# pulseAmplifier.net
KiCad netlist of a schematic drawn in Altium Designer
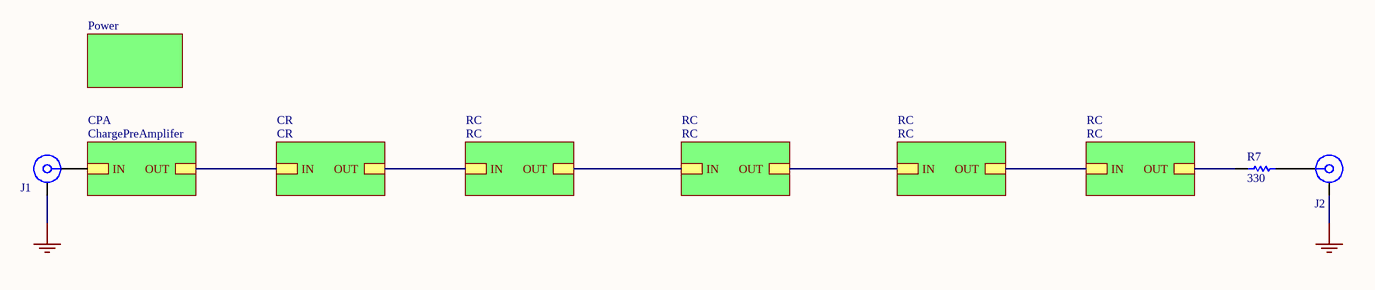
[diagram p0: pulseAmplifier.SchDoc]

(export (version "E")
  (design (tool "Eeschema 10.0.6"))
  (components
    (comp (ref "J1")
      (value "32K145-400L5")
      (footprint "ROS-32K145-400L5_V")
      (description "SMA Right Angle Jack, Edge Mount, Up to 18 GHz, -55 to 155 degC")
      (fields (field (name "MANUFACTURER") "Rosenberger"))
      (libsource (lib "Altium Content Vault") (part "ROS-CN-1F-RF1-A"))
    )
    (comp (ref "J2")
      (value "32K145-400L5")
      (footprint "ROS-32K145-400L5_V")
      (description "SMA Right Angle Jack, Edge Mount, Up to 18 GHz, -55 to 155 degC")
      (fields (field (name "MANUFACTURER") "Rosenberger"))
      (libsource (lib "Altium Content Vault") (part "ROS-CN-1F-RF1-A"))
    )
    (comp (ref "R7")
      (value "330")
      (footprint "RESC0603(1608)_N")
      (description "100R 0.1W 1% 0603 (1608 Metric)  SMD")
      (fields (field (name "TOLERANCE") "1 %") (field (name "POWER") "0.1 W"))
      (libsource (lib "Altium Content Vault") (part "RES"))
    )
  )
  (nets
    (net (code "1") (name "/IN") (class "Default")
      (node (ref "J1") (pin "1") (pinfunction "1_1") (pintype "passive"))
    )
    (net (code "7") (name "/OUT") (class "Default")
      (node (ref "R7") (pin "1") (pinfunction "1_1") (pintype "passive"))
    )
    (net (code "8") (name "GND") (class "Default")
      (node (ref "J1") (pin "MP") (pinfunction "MP_MP") (pintype "passive"))
      (node (ref "J2") (pin "MP") (pinfunction "MP_MP") (pintype "passive"))
    )
    (net (code "9") (name "Net-(J2-Pad1)") (class "Default")
      (node (ref "J2") (pin "1") (pinfunction "1_1") (pintype "passive"))
      (node (ref "R7") (pin "2") (pinfunction "2_2") (pintype "passive"))
    )
  )
)
